# Grove_-_Sliding_Potentiometer.net
KiCad netlist of a schematic drawn in EAGLE
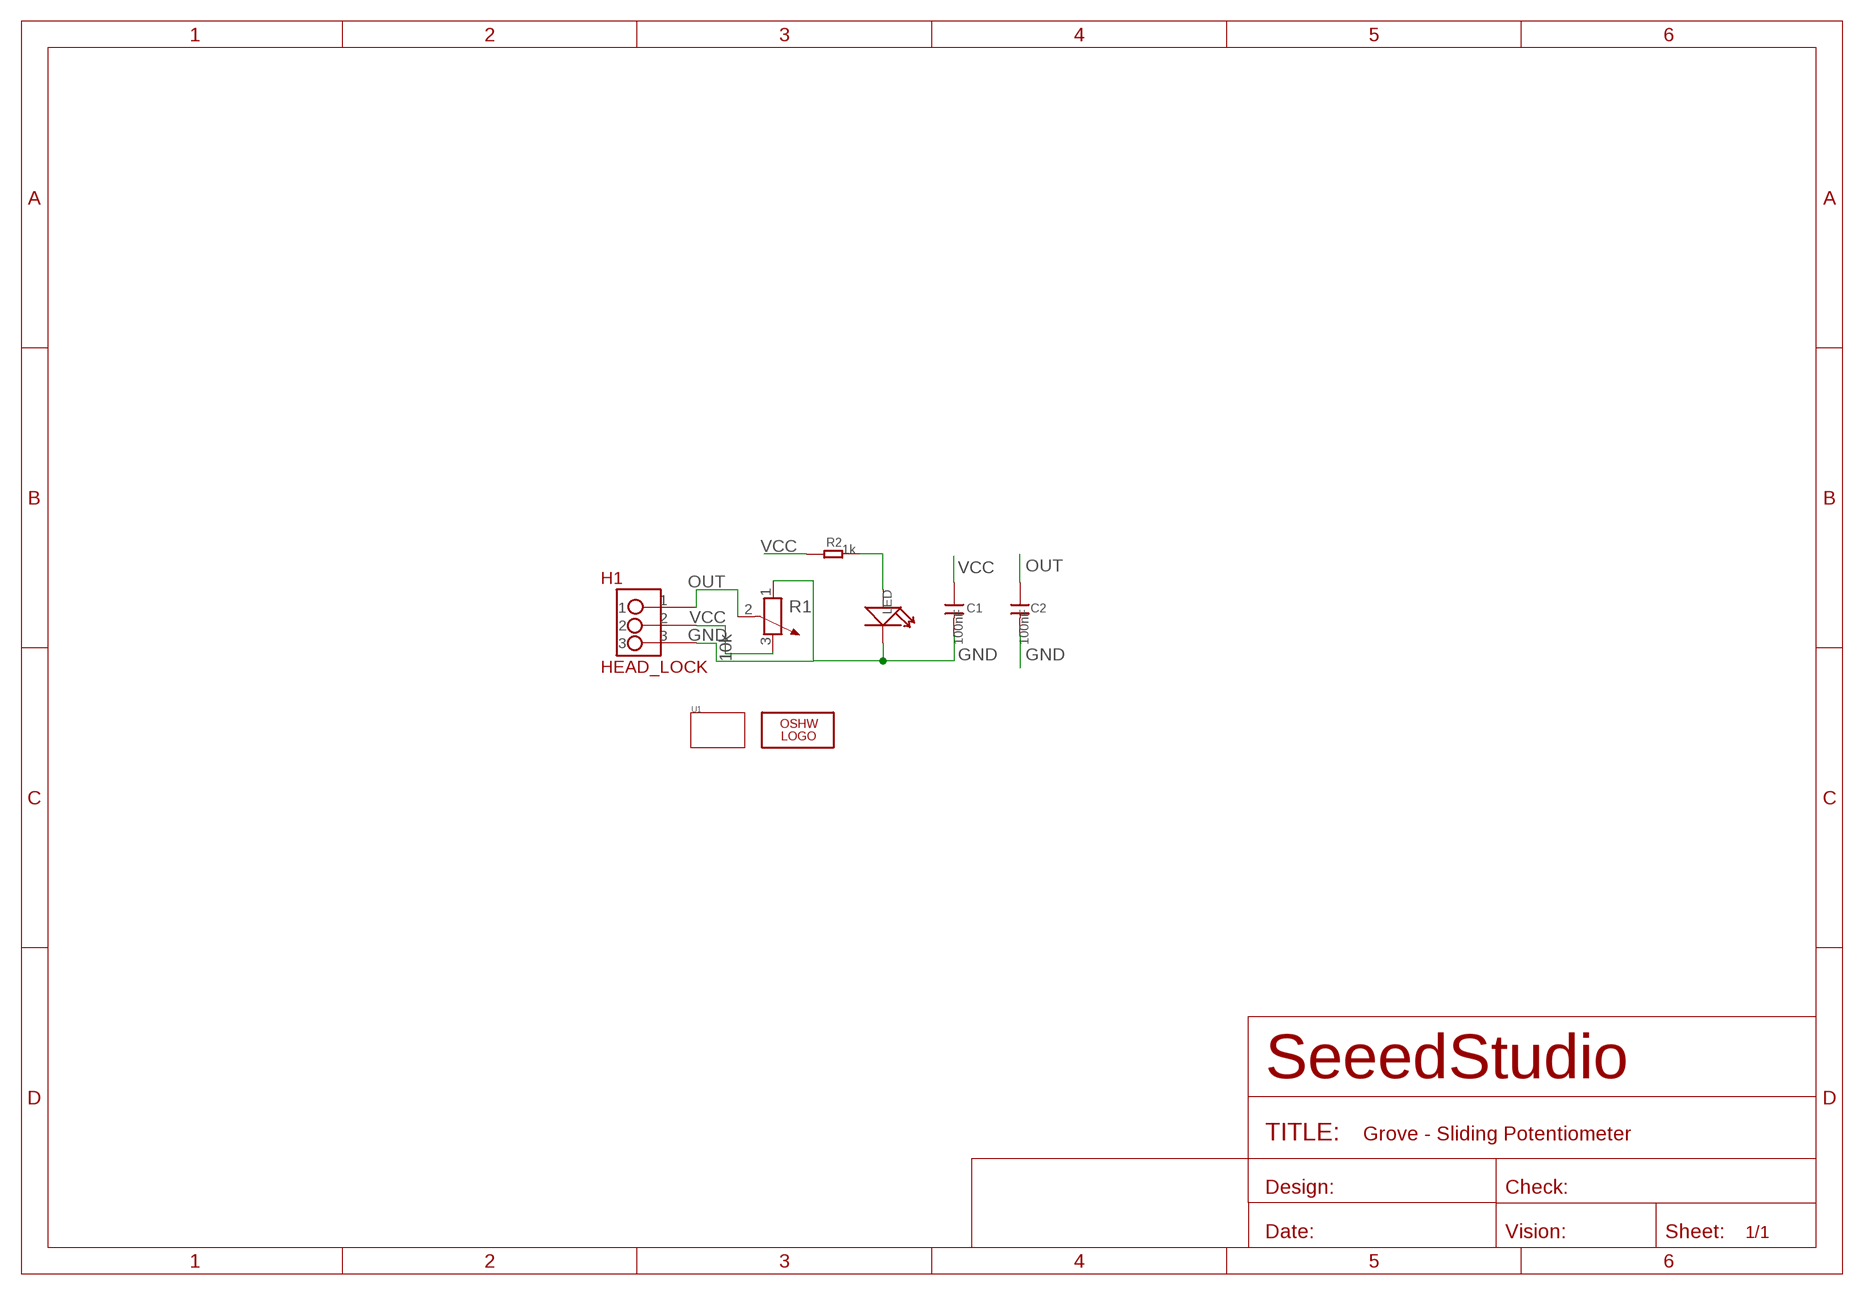
[diagram p0: schematic, sheet 1]

(export (version "E")
  (design (tool "Eeschema 10.0.6"))
  (components
    (comp (ref "C1")
      (value "100nF")
      (footprint "eagle-import:0805")
      (libsource (lib "eagle-import") (part "C-0805"))
    )
    (comp (ref "C2")
      (value "100nF")
      (footprint "eagle-import:0805")
      (libsource (lib "eagle-import") (part "C-0805"))
    )
    (comp (ref "H1")
      (value "HEAD_LOCK")
      (footprint "eagle-import:HEAD_LOCK")
      (libsource (lib "eagle-import") (part "HEAD_LOCK"))
    )
    (comp (ref "LED")
      (value "LED'0805'")
      (footprint "eagle-import:LED-0805")
      (libsource (lib "eagle-import") (part "LED'0805'"))
    )
    (comp (ref "LOGO1")
      (value "LOGO-OSHW-FILLX0200-NT")
      (footprint "eagle-import:OSHW_FILLX200_NOTEXT")
      (libsource (lib "eagle-import") (part "LOGO-OSHW-FILLX0200-NT"))
    )
    (comp (ref "R1")
      (value "10k")
      (footprint "eagle-import:3P-SQUA-45.6X10X5.8H")
      (libsource (lib "eagle-import") (part "R-POTENTIOMETER"))
    )
    (comp (ref "R2")
      (value "1k")
      (footprint "eagle-import:0805")
      (libsource (lib "eagle-import") (part "R-0805"))
    )
    (comp (ref "U1")
      (value "TWIG'3U'")
      (footprint "eagle-import:3U-DIM-W_-DRILL")
      (libsource (lib "eagle-import") (part "TWIG'3U'"))
    )
  )
  (nets
    (net (code "1") (name "/GND") (class "Default")
      (node (ref "C1") (pin "2") (pinfunction "2_2") (pintype "passive"))
      (node (ref "C2") (pin "2") (pinfunction "2_2") (pintype "passive"))
      (node (ref "H1") (pin "3") (pinfunction "3_3") (pintype "passive"))
      (node (ref "LED") (pin "-") (pinfunction "-_-") (pintype "passive"))
      (node (ref "R1") (pin "1") (pinfunction "1_1") (pintype "passive"))
    )
    (net (code "2") (name "/OUT") (class "Default")
      (node (ref "C2") (pin "1") (pinfunction "1_1") (pintype "passive"))
      (node (ref "H1") (pin "1") (pinfunction "1_1") (pintype "passive"))
      (node (ref "R1") (pin "2") (pinfunction "3_2") (pintype "passive"))
    )
    (net (code "3") (name "/VCC") (class "Default")
      (node (ref "C1") (pin "1") (pinfunction "1_1") (pintype "passive"))
      (node (ref "H1") (pin "2") (pinfunction "2_2") (pintype "passive"))
      (node (ref "R1") (pin "3") (pinfunction "2_3") (pintype "passive"))
    )
    (net (code "4") (name "Net-(LED-Pad+)") (class "Default")
      (node (ref "LED") (pin "+") (pinfunction "+_+") (pintype "passive"))
      (node (ref "R2") (pin "2") (pinfunction "2_2") (pintype "passive"))
    )
    (net (code "5") (name "unconnected-(R2-Pad1)") (class "Default")
      (node (ref "R2") (pin "1") (pinfunction "1_1") (pintype "passive"))
    )
  )
)
